# Main_Board.net
KiCad netlist of a schematic drawn in EAGLE
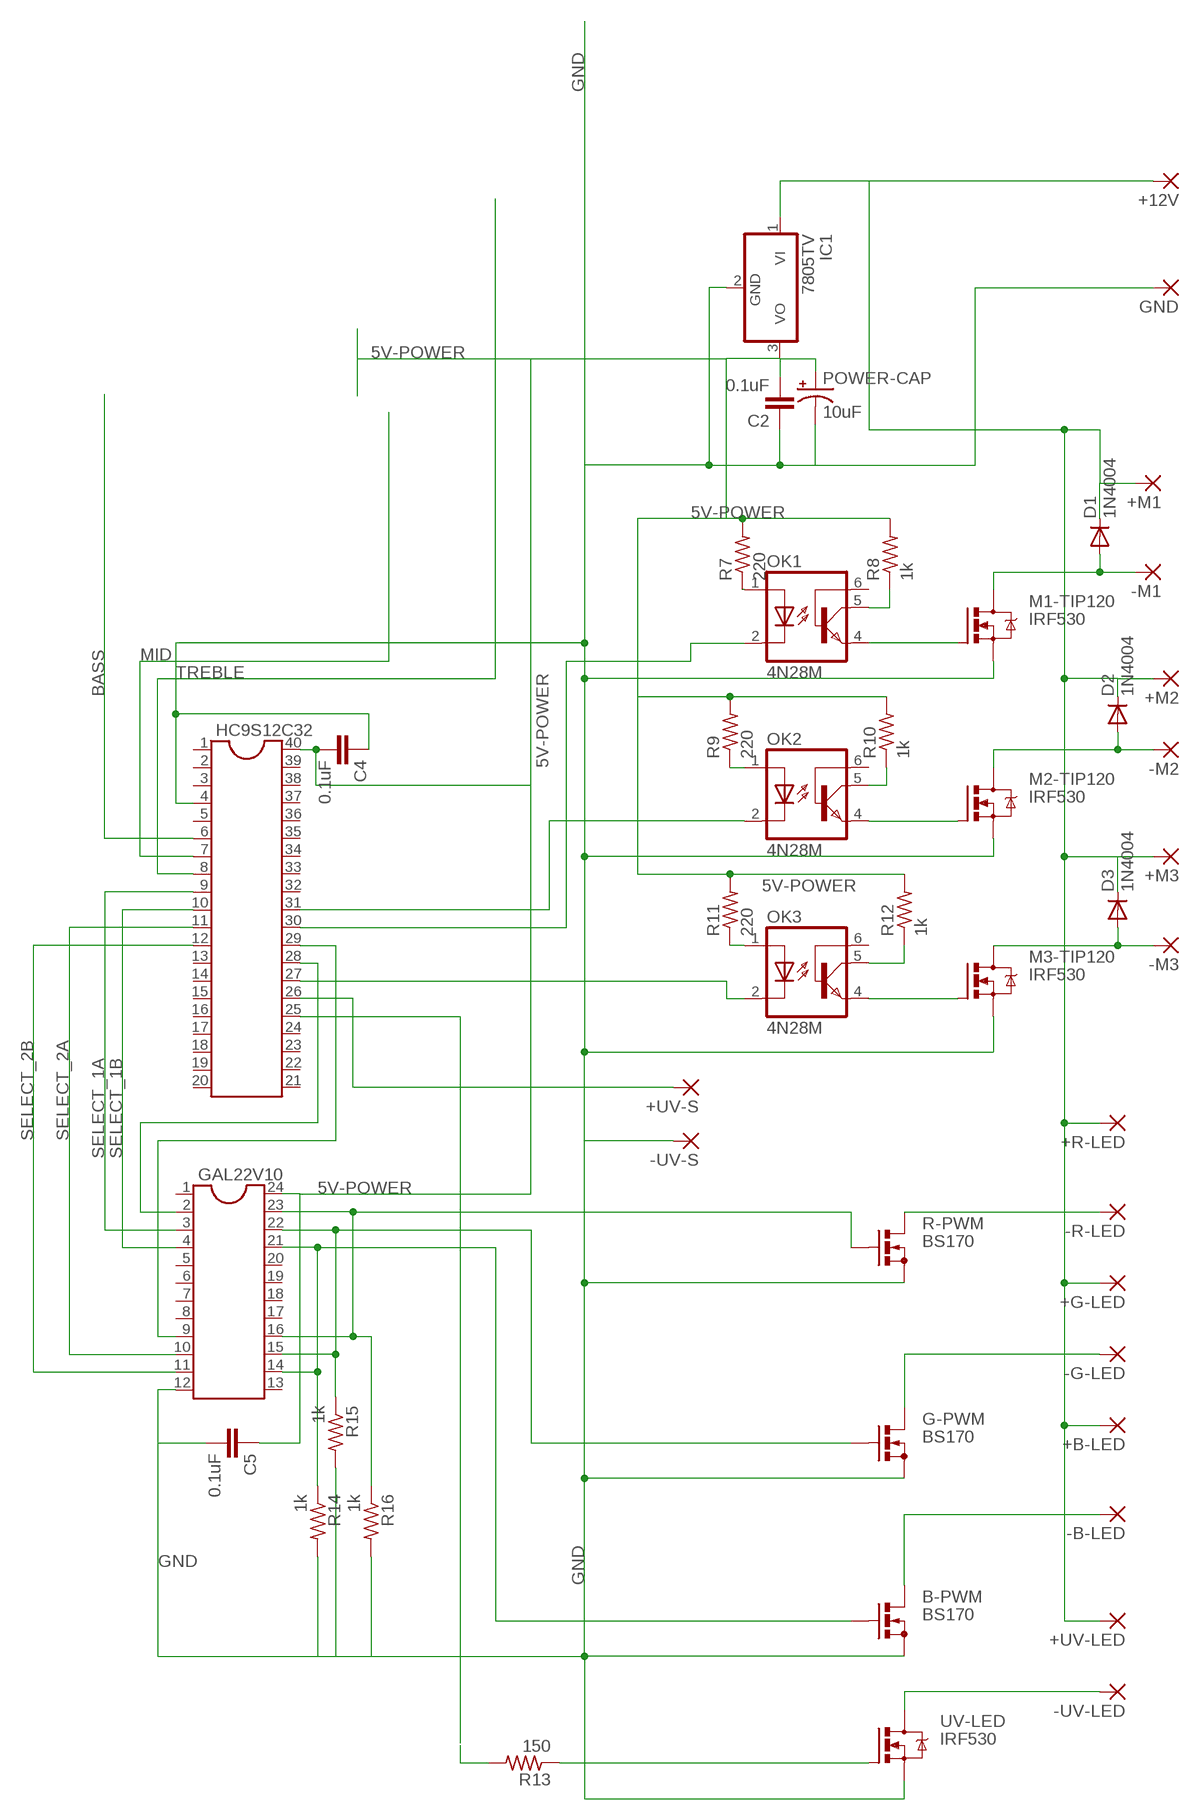
[diagram p0: schematic, sheet 1]

(export (version "E")
  (design (tool "Eeschema 10.0.6"))
  (components
    (comp (ref "+12V")
      (value "3,81/1,4")
      (footprint "eagle-import:3,81_1,4")
      (libsource (lib "eagle-import") (part "3,81/1,4"))
    )
    (comp (ref "+B-LED")
      (value "3,81/1,4")
      (footprint "eagle-import:3,81_1,4")
      (libsource (lib "eagle-import") (part "3,81/1,4"))
    )
    (comp (ref "+G-LED")
      (value "3,81/1,4")
      (footprint "eagle-import:3,81_1,4")
      (libsource (lib "eagle-import") (part "3,81/1,4"))
    )
    (comp (ref "+M1")
      (value "3,81/1,4")
      (footprint "eagle-import:3,81_1,4")
      (libsource (lib "eagle-import") (part "3,81/1,4"))
    )
    (comp (ref "+M2")
      (value "3,81/1,4")
      (footprint "eagle-import:3,81_1,4")
      (libsource (lib "eagle-import") (part "3,81/1,4"))
    )
    (comp (ref "+M3")
      (value "3,81/1,4")
      (footprint "eagle-import:3,81_1,4")
      (libsource (lib "eagle-import") (part "3,81/1,4"))
    )
    (comp (ref "+R-LED")
      (value "3,81/1,4")
      (footprint "eagle-import:3,81_1,4")
      (libsource (lib "eagle-import") (part "3,81/1,4"))
    )
    (comp (ref "+UV-LED")
      (value "3,81/1,4")
      (footprint "eagle-import:3,81_1,4")
      (libsource (lib "eagle-import") (part "3,81/1,4"))
    )
    (comp (ref "+UV-S")
      (value "3,81/1,4")
      (footprint "eagle-import:3,81_1,4")
      (libsource (lib "eagle-import") (part "3,81/1,4"))
    )
    (comp (ref "-B-LED")
      (value "3,81/1,4")
      (footprint "eagle-import:3,81_1,4")
      (libsource (lib "eagle-import") (part "3,81/1,4"))
    )
    (comp (ref "-G-LED")
      (value "3,81/1,4")
      (footprint "eagle-import:3,81_1,4")
      (libsource (lib "eagle-import") (part "3,81/1,4"))
    )
    (comp (ref "-M1")
      (value "3,81/1,4")
      (footprint "eagle-import:3,81_1,4")
      (libsource (lib "eagle-import") (part "3,81/1,4"))
    )
    (comp (ref "-M2")
      (value "3,81/1,4")
      (footprint "eagle-import:3,81_1,4")
      (libsource (lib "eagle-import") (part "3,81/1,4"))
    )
    (comp (ref "-M3")
      (value "3,81/1,4")
      (footprint "eagle-import:3,81_1,4")
      (libsource (lib "eagle-import") (part "3,81/1,4"))
    )
    (comp (ref "-R-LED")
      (value "3,81/1,4")
      (footprint "eagle-import:3,81_1,4")
      (libsource (lib "eagle-import") (part "3,81/1,4"))
    )
    (comp (ref "-UV-LED")
      (value "3,81/1,4")
      (footprint "eagle-import:3,81_1,4")
      (libsource (lib "eagle-import") (part "3,81/1,4"))
    )
    (comp (ref "-UV-S")
      (value "3,81/1,4")
      (footprint "eagle-import:3,81_1,4")
      (libsource (lib "eagle-import") (part "3,81/1,4"))
    )
    (comp (ref "B-PWM")
      (value "BS170")
      (footprint "eagle-import:SOT54E")
      (libsource (lib "eagle-import") (part "BS170"))
    )
    (comp (ref "C2")
      (value "0.1uF")
      (footprint "eagle-import:C7.5B6")
      (libsource (lib "eagle-import") (part "C7.5/6"))
    )
    (comp (ref "C4")
      (value "0.1uF")
      (footprint "eagle-import:C7.5B6")
      (libsource (lib "eagle-import") (part "C7.5/6"))
    )
    (comp (ref "C5")
      (value "0.1uF")
      (footprint "eagle-import:C7.5B6")
      (libsource (lib "eagle-import") (part "C7.5/6"))
    )
    (comp (ref "D1")
      (value "1N4004")
      (footprint "eagle-import:DO41-10")
      (libsource (lib "eagle-import") (part "1N4004"))
    )
    (comp (ref "D2")
      (value "1N4004")
      (footprint "eagle-import:DO41-10")
      (libsource (lib "eagle-import") (part "1N4004"))
    )
    (comp (ref "D3")
      (value "1N4004")
      (footprint "eagle-import:DO41-10")
      (libsource (lib "eagle-import") (part "1N4004"))
    )
    (comp (ref "G-PWM")
      (value "BS170")
      (footprint "eagle-import:SOT54E")
      (libsource (lib "eagle-import") (part "BS170"))
    )
    (comp (ref "GAL22V10")
      (value "DIL24-3")
      (footprint "eagle-import:DIL24-3")
      (libsource (lib "eagle-import") (part "DIL24-3"))
    )
    (comp (ref "GND")
      (value "3,81/1,4")
      (footprint "eagle-import:3,81_1,4")
      (libsource (lib "eagle-import") (part "3,81/1,4"))
    )
    (comp (ref "HC9S12C32")
      (value "DIL40")
      (footprint "eagle-import:DIL40")
      (libsource (lib "eagle-import") (part "DIL40"))
    )
    (comp (ref "IC1")
      (value "7805TV")
      (footprint "eagle-import:TO220V")
      (libsource (lib "eagle-import") (part "78TV05"))
    )
    (comp (ref "M1-TIP120")
      (value "IRF530")
      (footprint "eagle-import:TO220BV")
      (libsource (lib "eagle-import") (part "IRF530"))
    )
    (comp (ref "M2-TIP120")
      (value "IRF530")
      (footprint "eagle-import:TO220BV")
      (libsource (lib "eagle-import") (part "IRF530"))
    )
    (comp (ref "M3-TIP120")
      (value "IRF530")
      (footprint "eagle-import:TO220BV")
      (libsource (lib "eagle-import") (part "IRF530"))
    )
    (comp (ref "OK1")
      (value "4N28M")
      (footprint "eagle-import:DIL06")
      (fields (field (name "MF") "FAIRCHILD SEMICONDUCTOR") (field (name "MPN") "4N28-M"))
      (libsource (lib "eagle-import") (part "4N?M28"))
    )
    (comp (ref "OK2")
      (value "4N28M")
      (footprint "eagle-import:DIL06")
      (fields (field (name "MF") "FAIRCHILD SEMICONDUCTOR") (field (name "MPN") "4N28-M"))
      (libsource (lib "eagle-import") (part "4N?M28"))
    )
    (comp (ref "OK3")
      (value "4N28M")
      (footprint "eagle-import:DIL06")
      (fields (field (name "MF") "FAIRCHILD SEMICONDUCTOR") (field (name "MPN") "4N28-M"))
      (libsource (lib "eagle-import") (part "4N?M28"))
    )
    (comp (ref "POWER-CAP")
      (value "10uF")
      (footprint "eagle-import:TT5D10")
      (libsource (lib "eagle-import") (part "CPOL-USTT5D10"))
    )
    (comp (ref "R-PWM")
      (value "BS170")
      (footprint "eagle-import:SOT54E")
      (libsource (lib "eagle-import") (part "BS170"))
    )
    (comp (ref "R7")
      (value "220")
      (footprint "eagle-import:V234_12")
      (libsource (lib "eagle-import") (part "R-US_V234/12"))
    )
    (comp (ref "R8")
      (value "1k")
      (footprint "eagle-import:V234_12")
      (libsource (lib "eagle-import") (part "R-US_V234/12"))
    )
    (comp (ref "R9")
      (value "220")
      (footprint "eagle-import:V234_12")
      (libsource (lib "eagle-import") (part "R-US_V234/12"))
    )
    (comp (ref "R10")
      (value "1k")
      (footprint "eagle-import:V234_12")
      (libsource (lib "eagle-import") (part "R-US_V234/12"))
    )
    (comp (ref "R11")
      (value "220")
      (footprint "eagle-import:V234_12")
      (libsource (lib "eagle-import") (part "R-US_V234/12"))
    )
    (comp (ref "R12")
      (value "1k")
      (footprint "eagle-import:V234_12")
      (libsource (lib "eagle-import") (part "R-US_V234/12"))
    )
    (comp (ref "R13")
      (value "150")
      (footprint "eagle-import:V234_12")
      (libsource (lib "eagle-import") (part "R-US_V234/12"))
    )
    (comp (ref "R14")
      (value "1k")
      (footprint "eagle-import:V234_12")
      (libsource (lib "eagle-import") (part "R-US_V234/12"))
    )
    (comp (ref "R15")
      (value "1k")
      (footprint "eagle-import:V234_12")
      (libsource (lib "eagle-import") (part "R-US_V234/12"))
    )
    (comp (ref "R16")
      (value "1k")
      (footprint "eagle-import:V234_12")
      (libsource (lib "eagle-import") (part "R-US_V234/12"))
    )
    (comp (ref "UV-LED")
      (value "IRF530")
      (footprint "eagle-import:TO220BV")
      (libsource (lib "eagle-import") (part "IRF530"))
    )
  )
  (nets
    (net (code "1") (name "/5V-POWER") (class "Default")
      (node (ref "C2") (pin "2") (pinfunction "2_2") (pintype "passive"))
      (node (ref "C4") (pin "2") (pinfunction "2_2") (pintype "passive"))
      (node (ref "C5") (pin "1") (pinfunction "1_1") (pintype "passive"))
      (node (ref "GAL22V10") (pin "24") (pinfunction "24_24") (pintype "passive"))
      (node (ref "HC9S12C32") (pin "40") (pinfunction "40_40") (pintype "passive"))
      (node (ref "IC1") (pin "3") (pinfunction "VO_3") (pintype "passive"))
      (node (ref "POWER-CAP") (pin "+") (pinfunction "+_+") (pintype "passive"))
      (node (ref "R10") (pin "2") (pinfunction "2_2") (pintype "passive"))
      (node (ref "R11") (pin "2") (pinfunction "2_2") (pintype "passive"))
      (node (ref "R12") (pin "2") (pinfunction "2_2") (pintype "passive"))
      (node (ref "R7") (pin "2") (pinfunction "2_2") (pintype "passive"))
      (node (ref "R8") (pin "2") (pinfunction "2_2") (pintype "passive"))
      (node (ref "R9") (pin "2") (pinfunction "2_2") (pintype "passive"))
    )
    (net (code "2") (name "/BASS") (class "Default")
      (node (ref "HC9S12C32") (pin "6") (pinfunction "6_6") (pintype "passive"))
    )
    (net (code "3") (name "/GND") (class "Default")
      (node (ref "-UV-S") (pin "1") (pinfunction "P_1") (pintype "passive"))
      (node (ref "B-PWM") (pin "S") (pinfunction "S_S") (pintype "passive"))
      (node (ref "C2") (pin "1") (pinfunction "1_1") (pintype "passive"))
      (node (ref "C4") (pin "1") (pinfunction "1_1") (pintype "passive"))
      (node (ref "C5") (pin "2") (pinfunction "2_2") (pintype "passive"))
      (node (ref "G-PWM") (pin "S") (pinfunction "S_S") (pintype "passive"))
      (node (ref "GAL22V10") (pin "12") (pinfunction "12_12") (pintype "passive"))
      (node (ref "GND") (pin "1") (pinfunction "P_1") (pintype "passive"))
      (node (ref "HC9S12C32") (pin "4") (pinfunction "4_4") (pintype "passive"))
      (node (ref "IC1") (pin "2") (pinfunction "GND_2") (pintype "passive"))
      (node (ref "M1-TIP120") (pin "S") (pinfunction "S_S") (pintype "passive"))
      (node (ref "M2-TIP120") (pin "S") (pinfunction "S_S") (pintype "passive"))
      (node (ref "M3-TIP120") (pin "S") (pinfunction "S_S") (pintype "passive"))
      (node (ref "POWER-CAP") (pin "-") (pinfunction "-_-") (pintype "passive"))
      (node (ref "R-PWM") (pin "S") (pinfunction "S_S") (pintype "passive"))
      (node (ref "R14") (pin "2") (pinfunction "2_2") (pintype "passive"))
      (node (ref "R15") (pin "2") (pinfunction "2_2") (pintype "passive"))
      (node (ref "R16") (pin "2") (pinfunction "2_2") (pintype "passive"))
      (node (ref "UV-LED") (pin "S") (pinfunction "S_S") (pintype "passive"))
    )
    (net (code "4") (name "/MID") (class "Default")
      (node (ref "HC9S12C32") (pin "7") (pinfunction "7_7") (pintype "passive"))
    )
    (net (code "5") (name "/SELECT_1A") (class "Default")
      (node (ref "GAL22V10") (pin "3") (pinfunction "3_3") (pintype "passive"))
      (node (ref "HC9S12C32") (pin "9") (pinfunction "9_9") (pintype "passive"))
    )
    (net (code "6") (name "/SELECT_1B") (class "Default")
      (node (ref "GAL22V10") (pin "4") (pinfunction "4_4") (pintype "passive"))
      (node (ref "HC9S12C32") (pin "10") (pinfunction "10_10") (pintype "passive"))
    )
    (net (code "7") (name "/SELECT_2A") (class "Default")
      (node (ref "GAL22V10") (pin "10") (pinfunction "10_10") (pintype "passive"))
      (node (ref "HC9S12C32") (pin "11") (pinfunction "11_11") (pintype "passive"))
    )
    (net (code "8") (name "/SELECT_2B") (class "Default")
      (node (ref "GAL22V10") (pin "11") (pinfunction "11_11") (pintype "passive"))
      (node (ref "HC9S12C32") (pin "12") (pinfunction "12_12") (pintype "passive"))
    )
    (net (code "9") (name "/TREBLE") (class "Default")
      (node (ref "HC9S12C32") (pin "8") (pinfunction "8_8") (pintype "passive"))
    )
    (net (code "10") (name "Net-(+12V-P)") (class "Default")
      (node (ref "+12V") (pin "1") (pinfunction "P_1") (pintype "passive"))
      (node (ref "+B-LED") (pin "1") (pinfunction "P_1") (pintype "passive"))
      (node (ref "+G-LED") (pin "1") (pinfunction "P_1") (pintype "passive"))
      (node (ref "+M1") (pin "1") (pinfunction "P_1") (pintype "passive"))
      (node (ref "+M2") (pin "1") (pinfunction "P_1") (pintype "passive"))
      (node (ref "+M3") (pin "1") (pinfunction "P_1") (pintype "passive"))
      (node (ref "+R-LED") (pin "1") (pinfunction "P_1") (pintype "passive"))
      (node (ref "+UV-LED") (pin "1") (pinfunction "P_1") (pintype "passive"))
      (node (ref "D1") (pin "C") (pinfunction "C_C") (pintype "passive"))
      (node (ref "D2") (pin "C") (pinfunction "C_C") (pintype "passive"))
      (node (ref "D3") (pin "C") (pinfunction "C_C") (pintype "passive"))
      (node (ref "IC1") (pin "1") (pinfunction "VI_1") (pintype "input"))
    )
    (net (code "11") (name "Net-(+UV-S-P)") (class "Default")
      (node (ref "+UV-S") (pin "1") (pinfunction "P_1") (pintype "passive"))
      (node (ref "HC9S12C32") (pin "26") (pinfunction "26_26") (pintype "passive"))
    )
    (net (code "12") (name "Net-(-B-LED-P)") (class "Default")
      (node (ref "-B-LED") (pin "1") (pinfunction "P_1") (pintype "passive"))
      (node (ref "B-PWM") (pin "D") (pinfunction "D_D") (pintype "passive"))
    )
    (net (code "13") (name "Net-(-G-LED-P)") (class "Default")
      (node (ref "-G-LED") (pin "1") (pinfunction "P_1") (pintype "passive"))
      (node (ref "G-PWM") (pin "D") (pinfunction "D_D") (pintype "passive"))
    )
    (net (code "14") (name "Net-(-M1-P)") (class "Default")
      (node (ref "-M1") (pin "1") (pinfunction "P_1") (pintype "passive"))
      (node (ref "D1") (pin "A") (pinfunction "A_A") (pintype "passive"))
      (node (ref "M1-TIP120") (pin "D") (pinfunction "D_D") (pintype "passive"))
    )
    (net (code "15") (name "Net-(-M2-P)") (class "Default")
      (node (ref "-M2") (pin "1") (pinfunction "P_1") (pintype "passive"))
      (node (ref "D2") (pin "A") (pinfunction "A_A") (pintype "passive"))
      (node (ref "M2-TIP120") (pin "D") (pinfunction "D_D") (pintype "passive"))
    )
    (net (code "16") (name "Net-(-M3-P)") (class "Default")
      (node (ref "-M3") (pin "1") (pinfunction "P_1") (pintype "passive"))
      (node (ref "D3") (pin "A") (pinfunction "A_A") (pintype "passive"))
      (node (ref "M3-TIP120") (pin "D") (pinfunction "D_D") (pintype "passive"))
    )
    (net (code "17") (name "Net-(-R-LED-P)") (class "Default")
      (node (ref "-R-LED") (pin "1") (pinfunction "P_1") (pintype "passive"))
      (node (ref "R-PWM") (pin "D") (pinfunction "D_D") (pintype "passive"))
    )
    (net (code "18") (name "Net-(-UV-LED-P)") (class "Default")
      (node (ref "-UV-LED") (pin "1") (pinfunction "P_1") (pintype "passive"))
      (node (ref "UV-LED") (pin "D") (pinfunction "D_D") (pintype "passive"))
    )
    (net (code "19") (name "Net-(B-PWM-PadG)") (class "Default")
      (node (ref "B-PWM") (pin "G") (pinfunction "G_G") (pintype "passive"))
      (node (ref "GAL22V10") (pin "14") (pinfunction "14_14") (pintype "passive"))
      (node (ref "GAL22V10") (pin "21") (pinfunction "21_21") (pintype "passive"))
      (node (ref "R14") (pin "1") (pinfunction "1_1") (pintype "passive"))
    )
    (net (code "20") (name "Net-(G-PWM-PadG)") (class "Default")
      (node (ref "G-PWM") (pin "G") (pinfunction "G_G") (pintype "passive"))
      (node (ref "GAL22V10") (pin "15") (pinfunction "15_15") (pintype "passive"))
      (node (ref "GAL22V10") (pin "22") (pinfunction "22_22") (pintype "passive"))
      (node (ref "R15") (pin "1") (pinfunction "1_1") (pintype "passive"))
    )
    (net (code "21") (name "Net-(GAL22V10-Pad2)") (class "Default")
      (node (ref "GAL22V10") (pin "2") (pinfunction "2_2") (pintype "passive"))
      (node (ref "HC9S12C32") (pin "28") (pinfunction "28_28") (pintype "passive"))
    )
    (net (code "22") (name "Net-(GAL22V10-Pad9)") (class "Default")
      (node (ref "GAL22V10") (pin "9") (pinfunction "9_9") (pintype "passive"))
      (node (ref "HC9S12C32") (pin "29") (pinfunction "29_29") (pintype "passive"))
    )
    (net (code "23") (name "Net-(GAL22V10-Pad16)") (class "Default")
      (node (ref "GAL22V10") (pin "16") (pinfunction "16_16") (pintype "passive"))
      (node (ref "GAL22V10") (pin "23") (pinfunction "23_23") (pintype "passive"))
      (node (ref "R-PWM") (pin "G") (pinfunction "G_G") (pintype "passive"))
      (node (ref "R16") (pin "1") (pinfunction "1_1") (pintype "passive"))
    )
    (net (code "24") (name "Net-(OK1-A)") (class "Default")
      (node (ref "OK1") (pin "1") (pinfunction "A_1") (pintype "passive"))
      (node (ref "R7") (pin "1") (pinfunction "1_1") (pintype "passive"))
    )
    (net (code "25") (name "Net-(OK1-C)") (class "Default")
      (node (ref "HC9S12C32") (pin "30") (pinfunction "30_30") (pintype "passive"))
      (node (ref "OK1") (pin "2") (pinfunction "C_2") (pintype "passive"))
    )
    (net (code "26") (name "Net-(OK1-COL)") (class "Default")
      (node (ref "OK1") (pin "5") (pinfunction "COL_5") (pintype "passive"))
      (node (ref "R8") (pin "1") (pinfunction "1_1") (pintype "passive"))
    )
    (net (code "27") (name "Net-(OK1-EMI)") (class "Default")
      (node (ref "M1-TIP120") (pin "G") (pinfunction "G_G") (pintype "passive"))
      (node (ref "OK1") (pin "4") (pinfunction "EMI_4") (pintype "passive"))
    )
    (net (code "28") (name "Net-(OK2-A)") (class "Default")
      (node (ref "OK2") (pin "1") (pinfunction "A_1") (pintype "passive"))
      (node (ref "R9") (pin "1") (pinfunction "1_1") (pintype "passive"))
    )
    (net (code "29") (name "Net-(OK2-C)") (class "Default")
      (node (ref "HC9S12C32") (pin "31") (pinfunction "31_31") (pintype "passive"))
      (node (ref "OK2") (pin "2") (pinfunction "C_2") (pintype "passive"))
    )
    (net (code "30") (name "Net-(OK2-COL)") (class "Default")
      (node (ref "OK2") (pin "5") (pinfunction "COL_5") (pintype "passive"))
      (node (ref "R10") (pin "1") (pinfunction "1_1") (pintype "passive"))
    )
    (net (code "31") (name "Net-(OK2-EMI)") (class "Default")
      (node (ref "M2-TIP120") (pin "G") (pinfunction "G_G") (pintype "passive"))
      (node (ref "OK2") (pin "4") (pinfunction "EMI_4") (pintype "passive"))
    )
    (net (code "32") (name "Net-(OK3-A)") (class "Default")
      (node (ref "OK3") (pin "1") (pinfunction "A_1") (pintype "passive"))
      (node (ref "R11") (pin "1") (pinfunction "1_1") (pintype "passive"))
    )
    (net (code "33") (name "Net-(OK3-C)") (class "Default")
      (node (ref "HC9S12C32") (pin "27") (pinfunction "27_27") (pintype "passive"))
      (node (ref "OK3") (pin "2") (pinfunction "C_2") (pintype "passive"))
    )
    (net (code "34") (name "Net-(OK3-COL)") (class "Default")
      (node (ref "OK3") (pin "5") (pinfunction "COL_5") (pintype "passive"))
      (node (ref "R12") (pin "1") (pinfunction "1_1") (pintype "passive"))
    )
    (net (code "35") (name "Net-(OK3-EMI)") (class "Default")
      (node (ref "M3-TIP120") (pin "G") (pinfunction "G_G") (pintype "passive"))
      (node (ref "OK3") (pin "4") (pinfunction "EMI_4") (pintype "passive"))
    )
    (net (code "36") (name "Net-(R13-Pad1)") (class "Default")
      (node (ref "R13") (pin "1") (pinfunction "1_1") (pintype "passive"))
      (node (ref "UV-LED") (pin "G") (pinfunction "G_G") (pintype "passive"))
    )
    (net (code "37") (name "unconnected-(GAL22V10-Pad1)") (class "Default")
      (node (ref "GAL22V10") (pin "1") (pinfunction "1_1") (pintype "passive"))
    )
    (net (code "38") (name "unconnected-(GAL22V10-Pad5)") (class "Default")
      (node (ref "GAL22V10") (pin "5") (pinfunction "5_5") (pintype "passive"))
    )
    (net (code "39") (name "unconnected-(GAL22V10-Pad6)") (class "Default")
      (node (ref "GAL22V10") (pin "6") (pinfunction "6_6") (pintype "passive"))
    )
    (net (code "40") (name "unconnected-(GAL22V10-Pad7)") (class "Default")
      (node (ref "GAL22V10") (pin "7") (pinfunction "7_7") (pintype "passive"))
    )
    (net (code "41") (name "unconnected-(GAL22V10-Pad8)") (class "Default")
      (node (ref "GAL22V10") (pin "8") (pinfunction "8_8") (pintype "passive"))
    )
    (net (code "42") (name "unconnected-(GAL22V10-Pad13)") (class "Default")
      (node (ref "GAL22V10") (pin "13") (pinfunction "13_13") (pintype "passive"))
    )
    (net (code "43") (name "unconnected-(GAL22V10-Pad17)") (class "Default")
      (node (ref "GAL22V10") (pin "17") (pinfunction "17_17") (pintype "passive"))
    )
    (net (code "44") (name "unconnected-(GAL22V10-Pad18)") (class "Default")
      (node (ref "GAL22V10") (pin "18") (pinfunction "18_18") (pintype "passive"))
    )
    (net (code "45") (name "unconnected-(GAL22V10-Pad19)") (class "Default")
      (node (ref "GAL22V10") (pin "19") (pinfunction "19_19") (pintype "passive"))
    )
    (net (code "46") (name "unconnected-(GAL22V10-Pad20)") (class "Default")
      (node (ref "GAL22V10") (pin "20") (pinfunction "20_20") (pintype "passive"))
    )
    (net (code "47") (name "unconnected-(HC9S12C32-Pad1)") (class "Default")
      (node (ref "HC9S12C32") (pin "1") (pinfunction "1_1") (pintype "passive"))
    )
    (net (code "48") (name "unconnected-(HC9S12C32-Pad2)") (class "Default")
      (node (ref "HC9S12C32") (pin "2") (pinfunction "2_2") (pintype "passive"))
    )
    (net (code "49") (name "unconnected-(HC9S12C32-Pad3)") (class "Default")
      (node (ref "HC9S12C32") (pin "3") (pinfunction "3_3") (pintype "passive"))
    )
    (net (code "50") (name "unconnected-(HC9S12C32-Pad5)") (class "Default")
      (node (ref "HC9S12C32") (pin "5") (pinfunction "5_5") (pintype "passive"))
    )
    (net (code "51") (name "unconnected-(HC9S12C32-Pad13)") (class "Default")
      (node (ref "HC9S12C32") (pin "13") (pinfunction "13_13") (pintype "passive"))
    )
    (net (code "52") (name "unconnected-(HC9S12C32-Pad14)") (class "Default")
      (node (ref "HC9S12C32") (pin "14") (pinfunction "14_14") (pintype "passive"))
    )
    (net (code "53") (name "unconnected-(HC9S12C32-Pad15)") (class "Default")
      (node (ref "HC9S12C32") (pin "15") (pinfunction "15_15") (pintype "passive"))
    )
    (net (code "54") (name "unconnected-(HC9S12C32-Pad16)") (class "Default")
      (node (ref "HC9S12C32") (pin "16") (pinfunction "16_16") (pintype "passive"))
    )
    (net (code "55") (name "unconnected-(HC9S12C32-Pad17)") (class "Default")
      (node (ref "HC9S12C32") (pin "17") (pinfunction "17_17") (pintype "passive"))
    )
    (net (code "56") (name "unconnected-(HC9S12C32-Pad18)") (class "Default")
      (node (ref "HC9S12C32") (pin "18") (pinfunction "18_18") (pintype "passive"))
    )
    (net (code "57") (name "unconnected-(HC9S12C32-Pad19)") (class "Default")
      (node (ref "HC9S12C32") (pin "19") (pinfunction "19_19") (pintype "passive"))
    )
    (net (code "58") (name "unconnected-(HC9S12C32-Pad20)") (class "Default")
      (node (ref "HC9S12C32") (pin "20") (pinfunction "20_20") (pintype "passive"))
    )
    (net (code "59") (name "unconnected-(HC9S12C32-Pad21)") (class "Default")
      (node (ref "HC9S12C32") (pin "21") (pinfunction "21_21") (pintype "passive"))
    )
    (net (code "60") (name "unconnected-(HC9S12C32-Pad22)") (class "Default")
      (node (ref "HC9S12C32") (pin "22") (pinfunction "22_22") (pintype "passive"))
    )
    (net (code "61") (name "unconnected-(HC9S12C32-Pad23)") (class "Default")
      (node (ref "HC9S12C32") (pin "23") (pinfunction "23_23") (pintype "passive"))
    )
    (net (code "62") (name "unconnected-(HC9S12C32-Pad24)") (class "Default")
      (node (ref "HC9S12C32") (pin "24") (pinfunction "24_24") (pintype "passive"))
    )
    (net (code "63") (name "unconnected-(HC9S12C32-Pad25)") (class "Default")
      (node (ref "HC9S12C32") (pin "25") (pinfunction "25_25") (pintype "passive"))
    )
    (net (code "64") (name "unconnected-(HC9S12C32-Pad32)") (class "Default")
      (node (ref "HC9S12C32") (pin "32") (pinfunction "32_32") (pintype "passive"))
    )
    (net (code "65") (name "unconnected-(HC9S12C32-Pad33)") (class "Default")
      (node (ref "HC9S12C32") (pin "33") (pinfunction "33_33") (pintype "passive"))
    )
    (net (code "66") (name "unconnected-(HC9S12C32-Pad34)") (class "Default")
      (node (ref "HC9S12C32") (pin "34") (pinfunction "34_34") (pintype "passive"))
    )
    (net (code "67") (name "unconnected-(HC9S12C32-Pad35)") (class "Default")
      (node (ref "HC9S12C32") (pin "35") (pinfunction "35_35") (pintype "passive"))
    )
    (net (code "68") (name "unconnected-(HC9S12C32-Pad36)") (class "Default")
      (node (ref "HC9S12C32") (pin "36") (pinfunction "36_36") (pintype "passive"))
    )
    (net (code "69") (name "unconnected-(HC9S12C32-Pad37)") (class "Default")
      (node (ref "HC9S12C32") (pin "37") (pinfunction "37_37") (pintype "passive"))
    )
    (net (code "70") (name "unconnected-(HC9S12C32-Pad38)") (class "Default")
      (node (ref "HC9S12C32") (pin "38") (pinfunction "38_38") (pintype "passive"))
    )
    (net (code "71") (name "unconnected-(HC9S12C32-Pad39)") (class "Default")
      (node (ref "HC9S12C32") (pin "39") (pinfunction "39_39") (pintype "passive"))
    )
    (net (code "72") (name "unconnected-(OK1-BAS-Pad6)") (class "Default")
      (node (ref "OK1") (pin "6") (pinfunction "BAS_6") (pintype "passive"))
    )
    (net (code "73") (name "unconnected-(OK2-BAS-Pad6)") (class "Default")
      (node (ref "OK2") (pin "6") (pinfunction "BAS_6") (pintype "passive"))
    )
    (net (code "74") (name "unconnected-(OK3-BAS-Pad6)") (class "Default")
      (node (ref "OK3") (pin "6") (pinfunction "BAS_6") (pintype "passive"))
    )
    (net (code "75") (name "unconnected-(R13-Pad2)") (class "Default")
      (node (ref "R13") (pin "2") (pinfunction "2_2") (pintype "passive"))
    )
  )
)
